# workshop_pcb.net
KiCad netlist of a schematic drawn in EAGLE
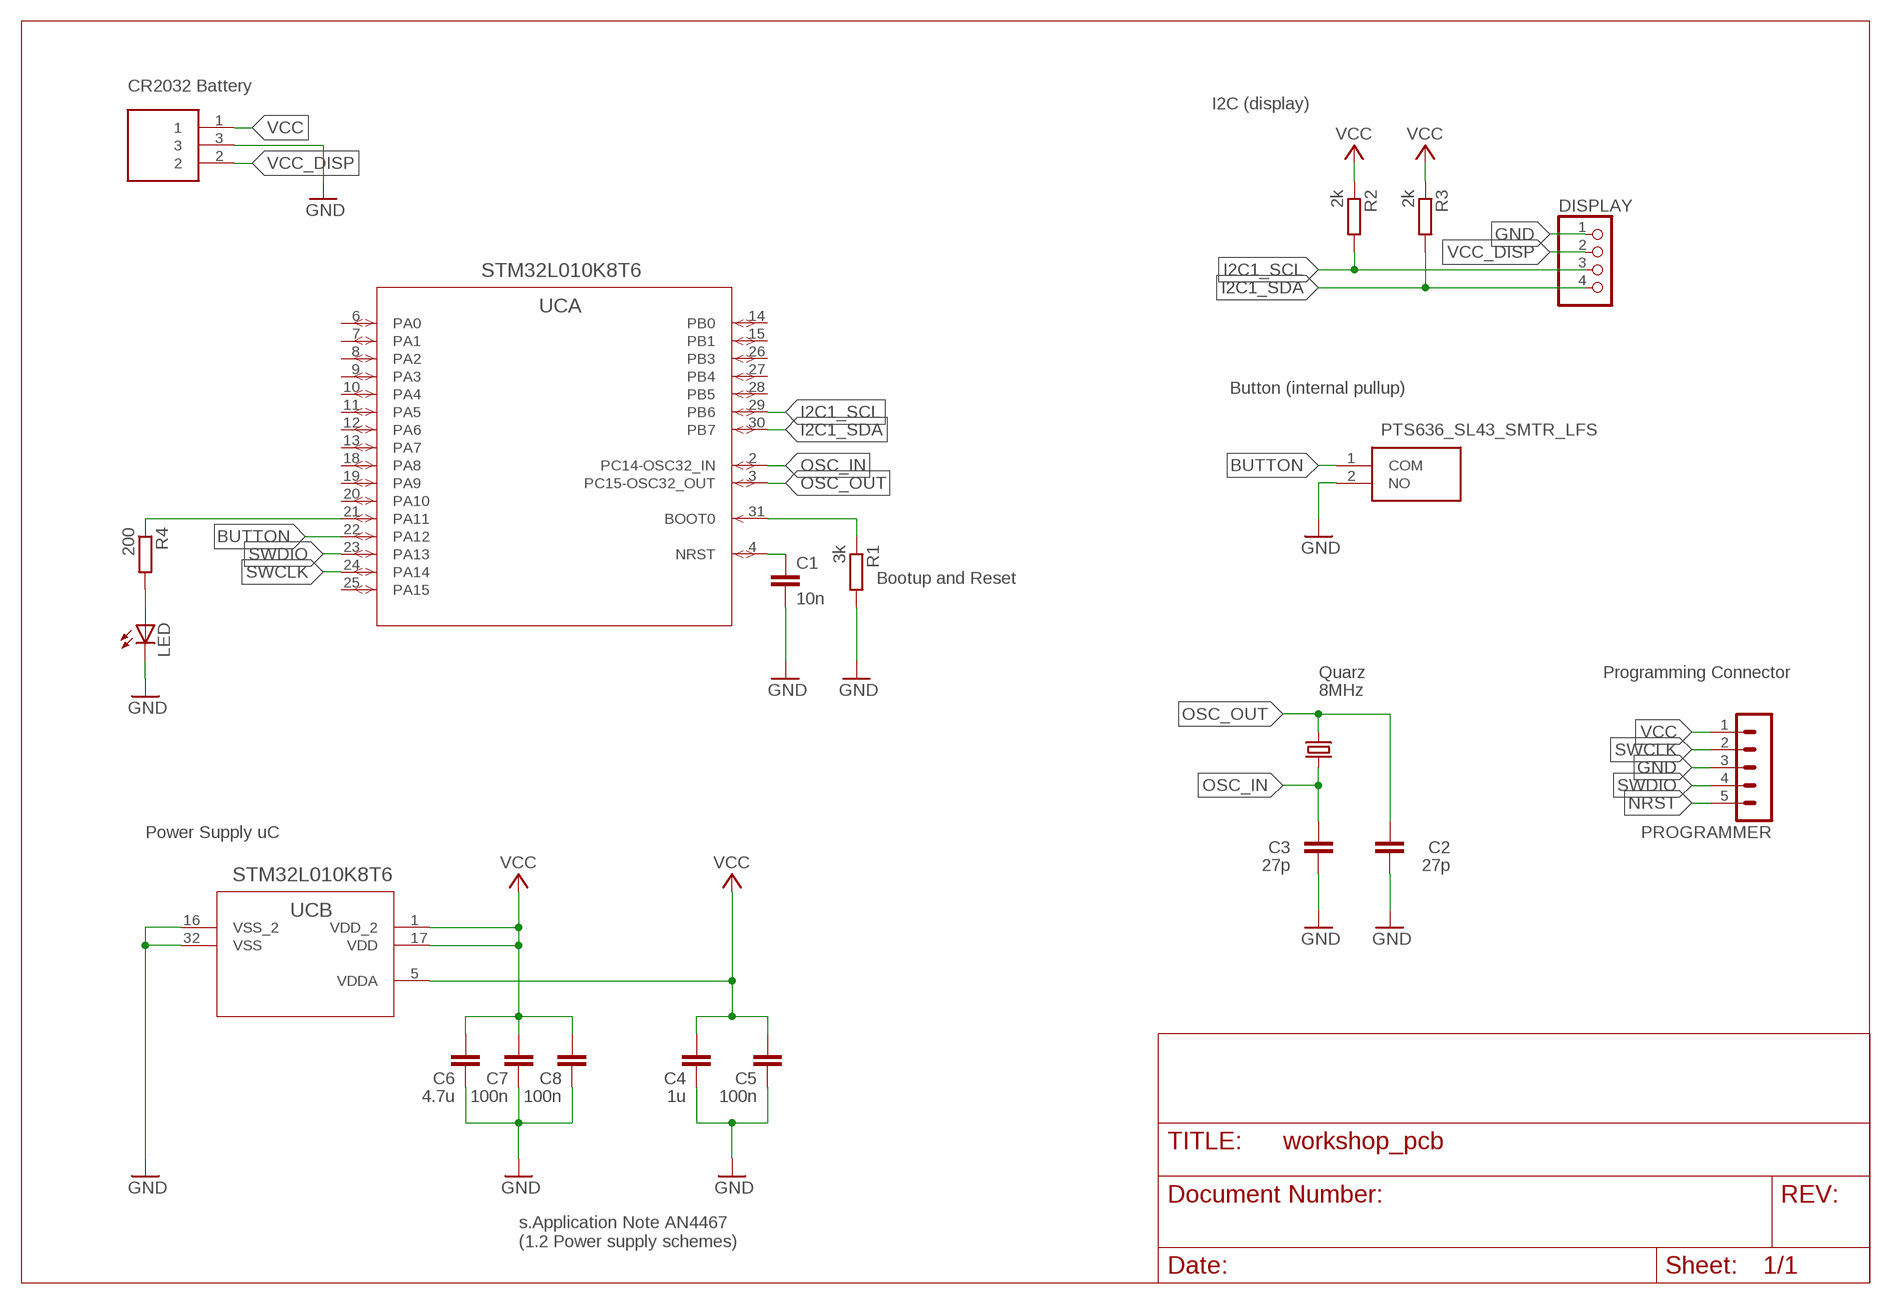
[diagram p0: schematic, sheet 1]

(export (version "E")
  (design (tool "Eeschema 10.0.6"))
  (components
    (comp (ref "BUTTON")
      (value "PTS636_SL43_SMTR_LFS")
      (footprint "eagle-import:PTS636SL43SMTRLFS")
      (fields
        (field (name "MANUFACTURER_PART_NUMBER") "PTS636 SL43 SMTR LFS")
        (field (name "MOUSER_PART_NUMBER") "611-PTS636SL43SMTRLF")
      )
      (libsource (lib "eagle-import") (part "PTS636_SL43_SMTR_LFS"))
    )
    (comp (ref "C1")
      (value "10n")
      (footprint "eagle-import:C0805")
      (libsource (lib "eagle-import") (part "C-EUC0805"))
    )
    (comp (ref "C2")
      (value "27p")
      (footprint "eagle-import:C0805")
      (libsource (lib "eagle-import") (part "C-EUC0805"))
    )
    (comp (ref "C3")
      (value "27p")
      (footprint "eagle-import:C0805")
      (libsource (lib "eagle-import") (part "C-EUC0805"))
    )
    (comp (ref "C4")
      (value "1u")
      (footprint "eagle-import:C0805")
      (libsource (lib "eagle-import") (part "C-EUC0805"))
    )
    (comp (ref "C5")
      (value "100n")
      (footprint "eagle-import:C0805")
      (libsource (lib "eagle-import") (part "C-EUC0805"))
    )
    (comp (ref "C6")
      (value "4.7u")
      (footprint "eagle-import:C0805")
      (libsource (lib "eagle-import") (part "C-EUC0805"))
    )
    (comp (ref "C7")
      (value "100n")
      (footprint "eagle-import:C0805")
      (libsource (lib "eagle-import") (part "C-EUC0805"))
    )
    (comp (ref "C8")
      (value "100n")
      (footprint "eagle-import:C0805")
      (libsource (lib "eagle-import") (part "C-EUC0805"))
    )
    (comp (ref "CR2032")
      (value "BAT-HLD-001")
      (footprint "eagle-import:BATHLD001")
      (fields (field (name "MOUSER_PART_NUMBER") "712-BAT-HLD-001"))
      (libsource (lib "eagle-import") (part "BAT-HLD-001"))
    )
    (comp (ref "DISPLAY")
      (value "PINHD-1X4")
      (footprint "eagle-import:1X04")
      (libsource (lib "eagle-import") (part "PINHD-1X4"))
    )
    (comp (ref "LED")
      (value "LEDCHIPLED_0805")
      (footprint "eagle-import:CHIPLED_0805")
      (libsource (lib "eagle-import") (part "LEDCHIPLED_0805"))
    )
    (comp (ref "PROGRAMMER")
      (value "MA05-1")
      (footprint "eagle-import:MA05-1")
      (libsource (lib "eagle-import") (part "MA05-1"))
    )
    (comp (ref "QUARZ")
      (value "8MHz")
      (footprint "eagle-import:HC49_S")
      (libsource (lib "eagle-import") (part "CRYSTALHC49S"))
    )
    (comp (ref "R1")
      (value "3k")
      (footprint "eagle-import:R0805")
      (libsource (lib "eagle-import") (part "R-EU_R0805"))
    )
    (comp (ref "R2")
      (value "2k")
      (footprint "eagle-import:R0805")
      (libsource (lib "eagle-import") (part "R-EU_R0805"))
    )
    (comp (ref "R3")
      (value "2k")
      (footprint "eagle-import:R0805")
      (libsource (lib "eagle-import") (part "R-EU_R0805"))
    )
    (comp (ref "R4")
      (value "200")
      (footprint "eagle-import:R0805")
      (libsource (lib "eagle-import") (part "R-EU_R0805"))
    )
    (comp (ref "UC")
      (value "STM32L010K8T6")
      (footprint "eagle-import:LQFP32_7X7X1P4")
      (fields (field (name "COPYRIGHT") "Copyright (C) 2018 Accelerated Designs. All rights reserved"))
      (libsource (lib "eagle-import") (part "STM32L010K8T6"))
    )
  )
  (nets
    (net (code "1") (name "BUTTON") (class "Default")
      (node (ref "BUTTON") (pin "1") (pinfunction "COM_1") (pintype "bidirectional"))
      (node (ref "UC") (pin "22") (pinfunction "PA12_22") (pintype "bidirectional"))
    )
    (net (code "2") (name "GND") (class "Default")
      (node (ref "BUTTON") (pin "2") (pinfunction "NO_2") (pintype "bidirectional"))
      (node (ref "C1") (pin "2") (pinfunction "2_2") (pintype "passive"))
      (node (ref "C2") (pin "1") (pinfunction "1_1") (pintype "passive"))
      (node (ref "C3") (pin "1") (pinfunction "1_1") (pintype "passive"))
      (node (ref "C4") (pin "1") (pinfunction "1_1") (pintype "passive"))
      (node (ref "C5") (pin "1") (pinfunction "1_1") (pintype "passive"))
      (node (ref "C6") (pin "1") (pinfunction "1_1") (pintype "passive"))
      (node (ref "C7") (pin "1") (pinfunction "1_1") (pintype "passive"))
      (node (ref "C8") (pin "1") (pinfunction "1_1") (pintype "passive"))
      (node (ref "CR2032") (pin "3") (pinfunction "3_3") (pintype "bidirectional"))
      (node (ref "DISPLAY") (pin "1") (pinfunction "1_1") (pintype "passive"))
      (node (ref "LED") (pin "C") (pinfunction "C_C") (pintype "passive"))
      (node (ref "PROGRAMMER") (pin "3") (pinfunction "3_3") (pintype "passive"))
      (node (ref "R1") (pin "2") (pinfunction "2_2") (pintype "passive"))
      (node (ref "UC") (pin "16") (pinfunction "VSS_2_16") (pintype "power_in"))
      (node (ref "UC") (pin "32") (pinfunction "VSS_32") (pintype "power_in"))
    )
    (net (code "3") (name "I2C1_SCL") (class "Default")
      (node (ref "DISPLAY") (pin "3") (pinfunction "3_3") (pintype "passive"))
      (node (ref "R2") (pin "2") (pinfunction "2_2") (pintype "passive"))
      (node (ref "UC") (pin "29") (pinfunction "PB6_29") (pintype "bidirectional"))
    )
    (net (code "4") (name "I2C1_SDA") (class "Default")
      (node (ref "DISPLAY") (pin "4") (pinfunction "4_4") (pintype "passive"))
      (node (ref "R3") (pin "2") (pinfunction "2_2") (pintype "passive"))
      (node (ref "UC") (pin "30") (pinfunction "PB7_30") (pintype "bidirectional"))
    )
    (net (code "5") (name "NRST") (class "Default")
      (node (ref "C1") (pin "1") (pinfunction "1_1") (pintype "passive"))
      (node (ref "PROGRAMMER") (pin "5") (pinfunction "5_5") (pintype "passive"))
      (node (ref "UC") (pin "4") (pinfunction "NRST_4") (pintype "bidirectional"))
    )
    (net (code "6") (name "Net-(LED-PadA)") (class "Default")
      (node (ref "LED") (pin "A") (pinfunction "A_A") (pintype "passive"))
      (node (ref "R4") (pin "2") (pinfunction "2_2") (pintype "passive"))
    )
    (net (code "7") (name "Net-(UCA-BOOT0)") (class "Default")
      (node (ref "R1") (pin "1") (pinfunction "1_1") (pintype "passive"))
      (node (ref "UC") (pin "31") (pinfunction "BOOT0_31") (pintype "input"))
    )
    (net (code "8") (name "Net-(UCA-PA11)") (class "Default")
      (node (ref "R4") (pin "1") (pinfunction "1_1") (pintype "passive"))
      (node (ref "UC") (pin "21") (pinfunction "PA11_21") (pintype "bidirectional"))
    )
    (net (code "9") (name "OSC_IN") (class "Default")
      (node (ref "C3") (pin "2") (pinfunction "2_2") (pintype "passive"))
      (node (ref "QUARZ") (pin "2") (pinfunction "2_2") (pintype "passive"))
      (node (ref "UC") (pin "2") (pinfunction "PC14-OSC32_IN_2") (pintype "bidirectional"))
    )
    (net (code "10") (name "OSC_OUT") (class "Default")
      (node (ref "C2") (pin "2") (pinfunction "2_2") (pintype "passive"))
      (node (ref "QUARZ") (pin "1") (pinfunction "1_1") (pintype "passive"))
      (node (ref "UC") (pin "3") (pinfunction "PC15-OSC32_OUT_3") (pintype "bidirectional"))
    )
    (net (code "11") (name "SWCLK") (class "Default")
      (node (ref "PROGRAMMER") (pin "2") (pinfunction "2_2") (pintype "passive"))
      (node (ref "UC") (pin "24") (pinfunction "PA14_24") (pintype "bidirectional"))
    )
    (net (code "12") (name "SWDIO") (class "Default")
      (node (ref "PROGRAMMER") (pin "4") (pinfunction "4_4") (pintype "passive"))
      (node (ref "UC") (pin "23") (pinfunction "PA13_23") (pintype "bidirectional"))
    )
    (net (code "13") (name "VCC") (class "Default")
      (node (ref "C4") (pin "2") (pinfunction "2_2") (pintype "passive"))
      (node (ref "C5") (pin "2") (pinfunction "2_2") (pintype "passive"))
      (node (ref "C6") (pin "2") (pinfunction "2_2") (pintype "passive"))
      (node (ref "C7") (pin "2") (pinfunction "2_2") (pintype "passive"))
      (node (ref "C8") (pin "2") (pinfunction "2_2") (pintype "passive"))
      (node (ref "CR2032") (pin "1") (pinfunction "1_1") (pintype "bidirectional"))
      (node (ref "PROGRAMMER") (pin "1") (pinfunction "1_1") (pintype "passive"))
      (node (ref "R2") (pin "1") (pinfunction "1_1") (pintype "passive"))
      (node (ref "R3") (pin "1") (pinfunction "1_1") (pintype "passive"))
      (node (ref "UC") (pin "1") (pinfunction "VDD_2_1") (pintype "power_in"))
      (node (ref "UC") (pin "17") (pinfunction "VDD_17") (pintype "power_in"))
      (node (ref "UC") (pin "5") (pinfunction "VDDA_5") (pintype "power_in"))
    )
    (net (code "14") (name "VCC_DISP") (class "Default")
      (node (ref "CR2032") (pin "2") (pinfunction "2_2") (pintype "bidirectional"))
      (node (ref "DISPLAY") (pin "2") (pinfunction "2_2") (pintype "passive"))
    )
    (net (code "15") (name "unconnected-(UCA-PA0-Pad6)") (class "Default")
      (node (ref "UC") (pin "6") (pinfunction "PA0_6") (pintype "bidirectional"))
    )
    (net (code "16") (name "unconnected-(UCA-PA1-Pad7)") (class "Default")
      (node (ref "UC") (pin "7") (pinfunction "PA1_7") (pintype "bidirectional"))
    )
    (net (code "17") (name "unconnected-(UCA-PA2-Pad8)") (class "Default")
      (node (ref "UC") (pin "8") (pinfunction "PA2_8") (pintype "bidirectional"))
    )
    (net (code "18") (name "unconnected-(UCA-PA3-Pad9)") (class "Default")
      (node (ref "UC") (pin "9") (pinfunction "PA3_9") (pintype "bidirectional"))
    )
    (net (code "19") (name "unconnected-(UCA-PA4-Pad10)") (class "Default")
      (node (ref "UC") (pin "10") (pinfunction "PA4_10") (pintype "bidirectional"))
    )
    (net (code "20") (name "unconnected-(UCA-PA5-Pad11)") (class "Default")
      (node (ref "UC") (pin "11") (pinfunction "PA5_11") (pintype "bidirectional"))
    )
    (net (code "21") (name "unconnected-(UCA-PA6-Pad12)") (class "Default")
      (node (ref "UC") (pin "12") (pinfunction "PA6_12") (pintype "bidirectional"))
    )
    (net (code "22") (name "unconnected-(UCA-PA7-Pad13)") (class "Default")
      (node (ref "UC") (pin "13") (pinfunction "PA7_13") (pintype "bidirectional"))
    )
    (net (code "23") (name "unconnected-(UCA-PA8-Pad18)") (class "Default")
      (node (ref "UC") (pin "18") (pinfunction "PA8_18") (pintype "bidirectional"))
    )
    (net (code "24") (name "unconnected-(UCA-PA9-Pad19)") (class "Default")
      (node (ref "UC") (pin "19") (pinfunction "PA9_19") (pintype "bidirectional"))
    )
    (net (code "25") (name "unconnected-(UCA-PA10-Pad20)") (class "Default")
      (node (ref "UC") (pin "20") (pinfunction "PA10_20") (pintype "bidirectional"))
    )
    (net (code "26") (name "unconnected-(UCA-PA15-Pad25)") (class "Default")
      (node (ref "UC") (pin "25") (pinfunction "PA15_25") (pintype "bidirectional"))
    )
    (net (code "27") (name "unconnected-(UCA-PB0-Pad14)") (class "Default")
      (node (ref "UC") (pin "14") (pinfunction "PB0_14") (pintype "bidirectional"))
    )
    (net (code "28") (name "unconnected-(UCA-PB1-Pad15)") (class "Default")
      (node (ref "UC") (pin "15") (pinfunction "PB1_15") (pintype "bidirectional"))
    )
    (net (code "29") (name "unconnected-(UCA-PB3-Pad26)") (class "Default")
      (node (ref "UC") (pin "26") (pinfunction "PB3_26") (pintype "bidirectional"))
    )
    (net (code "30") (name "unconnected-(UCA-PB4-Pad27)") (class "Default")
      (node (ref "UC") (pin "27") (pinfunction "PB4_27") (pintype "bidirectional"))
    )
    (net (code "31") (name "unconnected-(UCA-PB5-Pad28)") (class "Default")
      (node (ref "UC") (pin "28") (pinfunction "PB5_28") (pintype "bidirectional"))
    )
  )
)
